# Schematic1.net
KiCad netlist of a schematic drawn in EasyEDA Pro
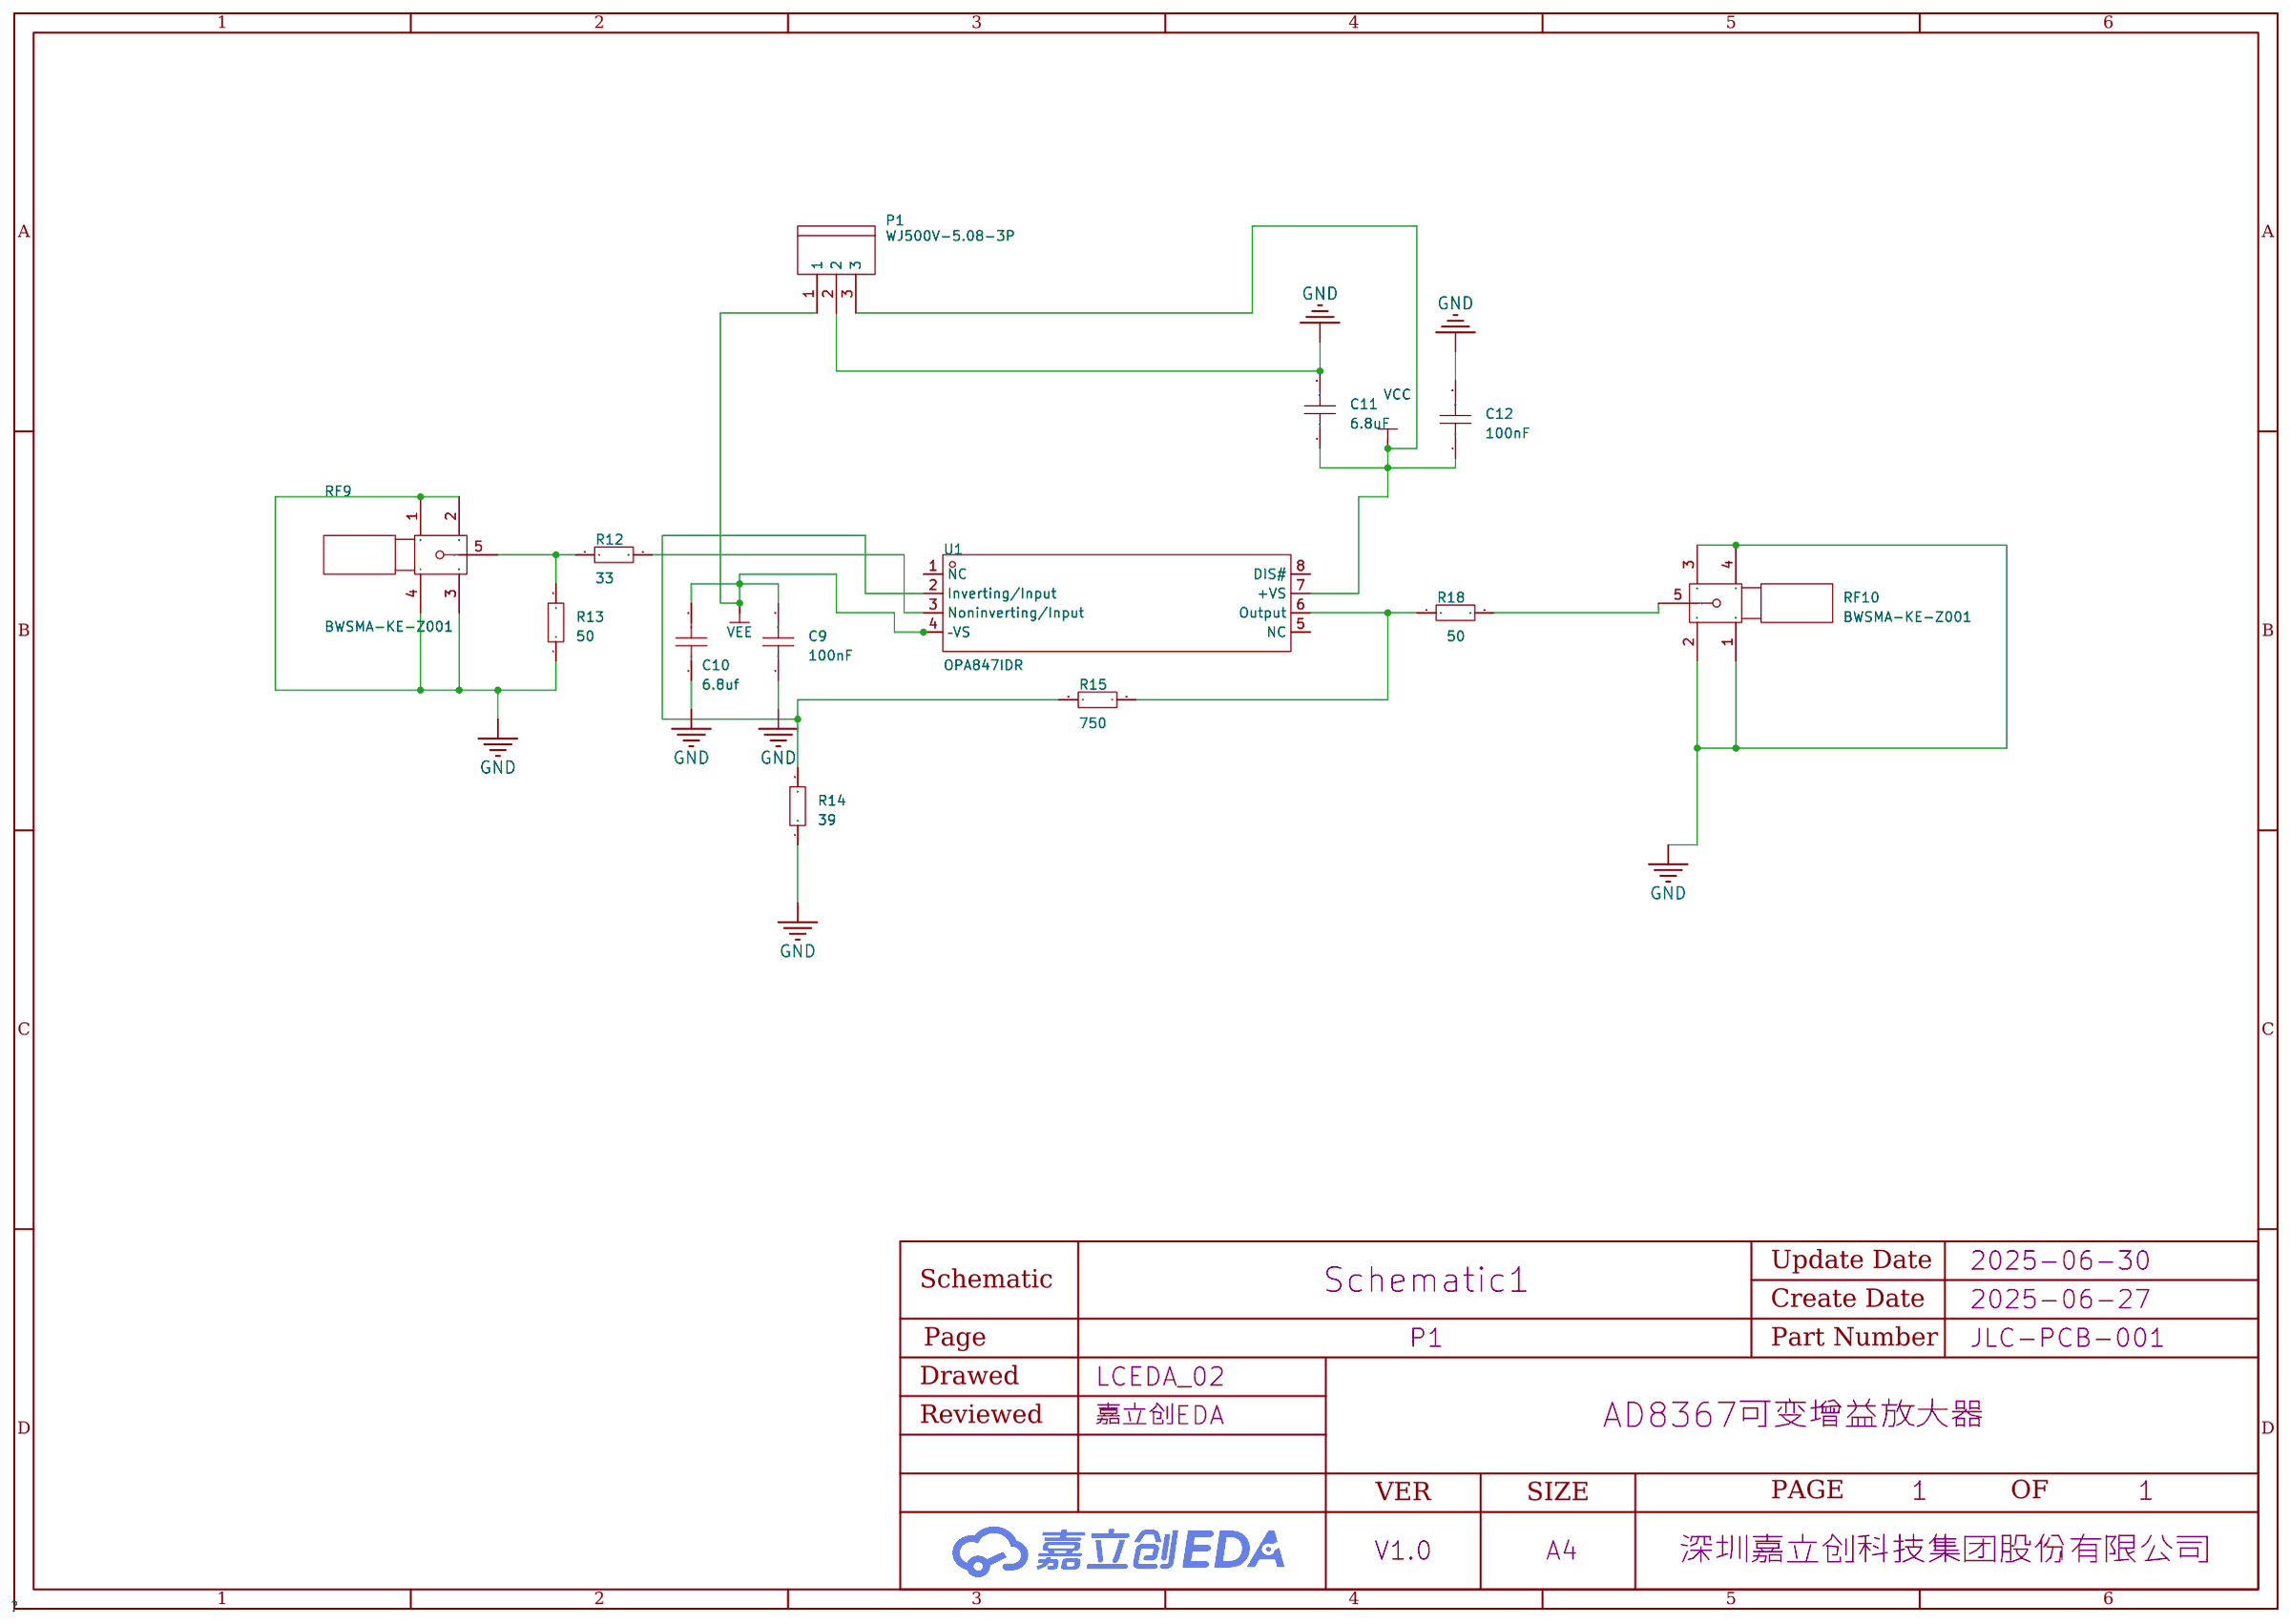
[diagram p0: schematic sheet]

(export (version "E")
  (design (tool "Eeschema 10.0.6"))
  (components
    (comp (ref "C9")
      (value "100nF")
      (footprint "easyedapro:C0805")
      (libsource (lib "easyedapro") (part "CapAcitance"))
    )
    (comp (ref "C10")
      (value "6.8uf")
      (footprint "easyedapro:C0805")
      (libsource (lib "easyedapro") (part "CapAcitance"))
    )
    (comp (ref "C11")
      (value "6.8uF")
      (footprint "easyedapro:C0805")
      (libsource (lib "easyedapro") (part "CapAcitance"))
    )
    (comp (ref "C12")
      (value "100nF")
      (footprint "easyedapro:C0805")
      (libsource (lib "easyedapro") (part "CapAcitance"))
    )
    (comp (ref "P1")
      (value "WJ500V-5.08-3P")
      (footprint "easyedapro:CONN-TH_3P-P5.00_WJ500V-5.08-3P")
      (fields (field (name "Manufacturer") "KANGNEX(康奈克斯电气)"))
      (libsource (lib "easyedapro") (part "WJ500V-5.08-3P-14-00A"))
    )
    (comp (ref "R12") (value "33") (footprint "easyedapro:R0805") (libsource (lib "easyedapro") (part "电阻")))
    (comp (ref "R13") (value "50") (footprint "easyedapro:R0805") (libsource (lib "easyedapro") (part "电阻")))
    (comp (ref "R14") (value "39") (footprint "easyedapro:R0805") (libsource (lib "easyedapro") (part "电阻")))
    (comp (ref "R15") (value "750") (footprint "easyedapro:R0805") (libsource (lib "easyedapro") (part "电阻")))
    (comp (ref "R18") (value "50") (footprint "easyedapro:R0805") (libsource (lib "easyedapro") (part "电阻")))
    (comp (ref "RF9")
      (value "BWSMA-KE-Z001")
      (footprint "easyedapro:SMA-TH_BWSMA-KE-Z001")
      (fields (field (name "Manufacturer") "BAT WIRELESS(蝙蝠无线)"))
      (libsource (lib "easyedapro") (part "BWSMA-KE-Z001"))
    )
    (comp (ref "RF10")
      (value "BWSMA-KE-Z001")
      (footprint "easyedapro:SMA-TH_BWSMA-KE-Z001")
      (fields (field (name "Manufacturer") "BAT WIRELESS(蝙蝠无线)"))
      (libsource (lib "easyedapro") (part "BWSMA-KE-Z001"))
    )
    (comp (ref "U1")
      (value "OPA847IDR")
      (footprint "easyedapro:SOIC-8_L4.9-W3.9-P1.27-LS6.0-TL")
      (description "放大器数:单路;增益带宽积(GBP):3.9GHz;压摆率(SR):950V/us;输入偏置电流(Ib):19uA;")
      (fields (field (name "Manufacturer") "TI(德州仪器)"))
      (libsource (lib "easyedapro") (part "OPA847IDR"))
    )
  )
  (nets
    (net (code "1") (name "GND") (class "Default")
      (node (ref "C10") (pin "1") (pinfunction "1_1") (pintype "input"))
      (node (ref "C11") (pin "2") (pinfunction "2_2") (pintype "input"))
      (node (ref "C12") (pin "2") (pinfunction "2_2") (pintype "input"))
      (node (ref "C9") (pin "1") (pinfunction "1_1") (pintype "input"))
      (node (ref "P1") (pin "2") (pinfunction "2_2") (pintype "unspecified"))
      (node (ref "R13") (pin "1") (pinfunction "1_1") (pintype "input"))
      (node (ref "R14") (pin "1") (pinfunction "1_1") (pintype "input"))
      (node (ref "RF10") (pin "1") (pinfunction "1_1") (pintype "unspecified"))
      (node (ref "RF10") (pin "2") (pinfunction "2_2") (pintype "unspecified"))
      (node (ref "RF10") (pin "3") (pinfunction "3_3") (pintype "unspecified"))
      (node (ref "RF10") (pin "4") (pinfunction "4_4") (pintype "unspecified"))
      (node (ref "RF9") (pin "1") (pinfunction "1_1") (pintype "unspecified"))
      (node (ref "RF9") (pin "2") (pinfunction "2_2") (pintype "unspecified"))
      (node (ref "RF9") (pin "3") (pinfunction "3_3") (pintype "unspecified"))
      (node (ref "RF9") (pin "4") (pinfunction "4_4") (pintype "unspecified"))
    )
    (net (code "2") (name "Net-(R12-Pad1)") (class "Default")
      (node (ref "R12") (pin "1") (pinfunction "1_1") (pintype "input"))
      (node (ref "R13") (pin "2") (pinfunction "2_2") (pintype "input"))
      (node (ref "RF9") (pin "5") (pinfunction "5_5") (pintype "unspecified"))
    )
    (net (code "3") (name "Net-(R18-Pad2)") (class "Default")
      (node (ref "R18") (pin "2") (pinfunction "2_2") (pintype "input"))
      (node (ref "RF10") (pin "5") (pinfunction "5_5") (pintype "unspecified"))
    )
    (net (code "4") (name "Net-(U1-Inverting{slash}Input)") (class "Default")
      (node (ref "R14") (pin "2") (pinfunction "2_2") (pintype "input"))
      (node (ref "R15") (pin "1") (pinfunction "1_1") (pintype "input"))
      (node (ref "U1") (pin "2") (pinfunction "Inverting/Input_2") (pintype "unspecified"))
    )
    (net (code "5") (name "Net-(U1-Noninverting{slash}Input)") (class "Default")
      (node (ref "R12") (pin "2") (pinfunction "2_2") (pintype "input"))
      (node (ref "U1") (pin "3") (pinfunction "Noninverting/Input_3") (pintype "unspecified"))
    )
    (net (code "6") (name "Net-(U1-Output)") (class "Default")
      (node (ref "R15") (pin "2") (pinfunction "2_2") (pintype "input"))
      (node (ref "R18") (pin "1") (pinfunction "1_1") (pintype "input"))
      (node (ref "U1") (pin "6") (pinfunction "Output_6") (pintype "unspecified"))
    )
    (net (code "7") (name "VCC") (class "Default")
      (node (ref "C11") (pin "1") (pinfunction "1_1") (pintype "input"))
      (node (ref "C12") (pin "1") (pinfunction "1_1") (pintype "input"))
      (node (ref "P1") (pin "3") (pinfunction "3_3") (pintype "unspecified"))
      (node (ref "U1") (pin "7") (pinfunction "+VS_7") (pintype "unspecified"))
    )
    (net (code "8") (name "VEE") (class "Default")
      (node (ref "C10") (pin "2") (pinfunction "2_2") (pintype "input"))
      (node (ref "C9") (pin "2") (pinfunction "2_2") (pintype "input"))
      (node (ref "P1") (pin "1") (pinfunction "1_1") (pintype "unspecified"))
      (node (ref "U1") (pin "4") (pinfunction "–VS_4") (pintype "unspecified"))
    )
    (net (code "9") (name "unconnected-(U1-DIS#-Pad8)") (class "Default")
      (node (ref "U1") (pin "8") (pinfunction "DIS#_8") (pintype "unspecified"))
    )
    (net (code "10") (name "unconnected-(U1-NC-Pad1)") (class "Default")
      (node (ref "U1") (pin "1") (pinfunction "NC_1") (pintype "unspecified"))
    )
    (net (code "11") (name "unconnected-(U1-NC-Pad5)") (class "Default")
      (node (ref "U1") (pin "5") (pinfunction "NC_5") (pintype "unspecified"))
    )
  )
)
